# 1A18J6_1A20J11_A.net
KiCad netlist of a schematic drawn in Altium Designer
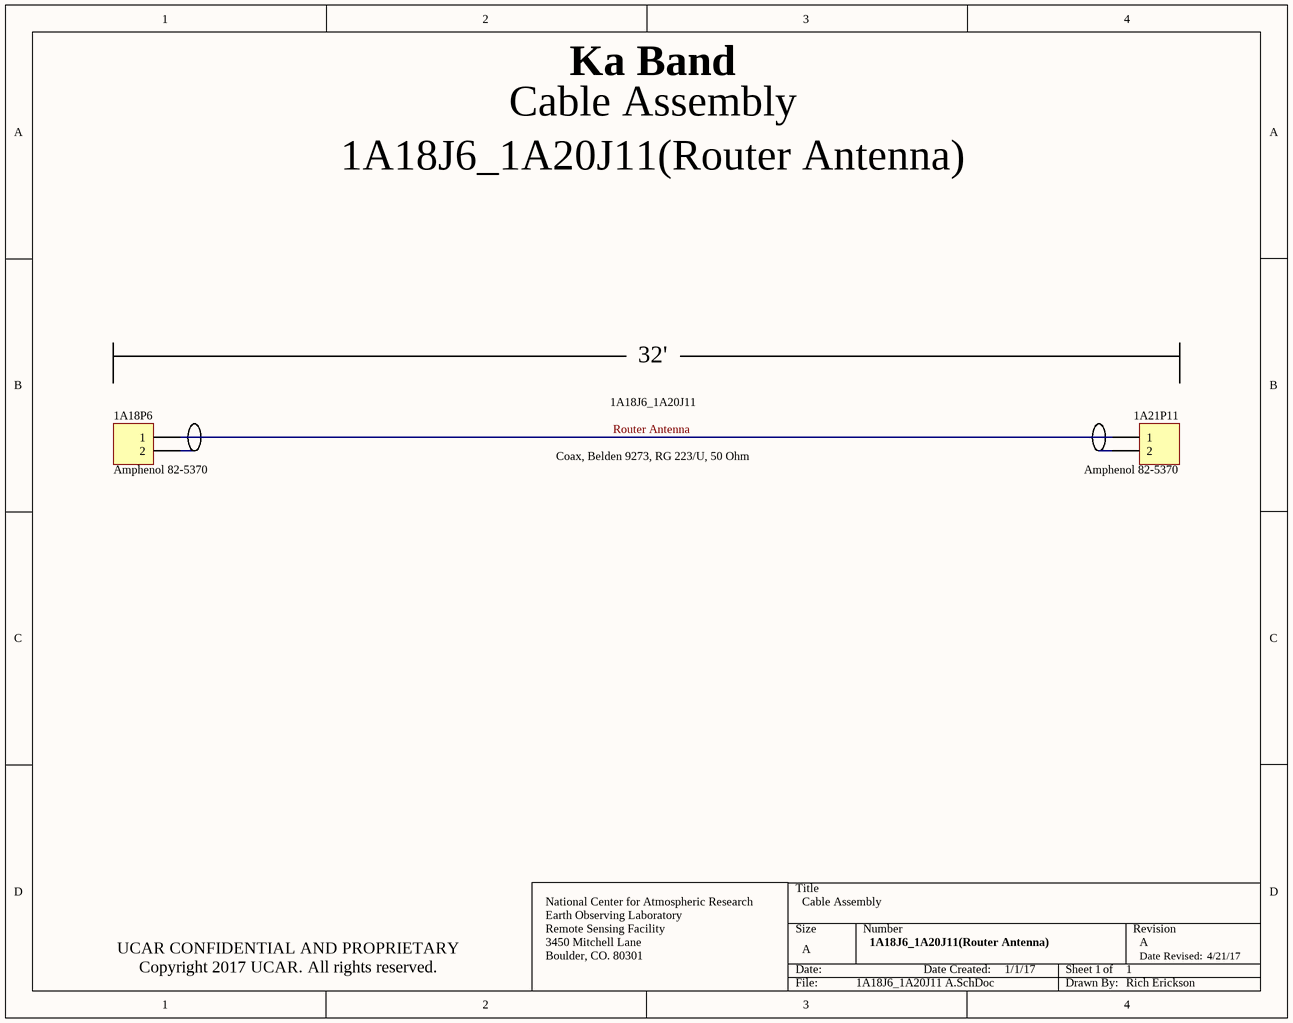
[diagram p0: 1A18J6_1A20J11 A.SchDoc]

(export (version "E")
  (design (tool "Eeschema 10.0.6"))
  (components
    (comp (ref "1A18P6")
      (value "Amphenol 82-5370")
      (footprint "HDR1X2")
      (description "Header, 2-Pin")
      (fields (field (name "PUBLISHER") "Altium Limited"))
      (libsource (lib "") (part "Header 2_1"))
    )
    (comp (ref "1A21P11")
      (value "Amphenol 82-5370")
      (footprint "HDR1X2")
      (description "Header, 2-Pin")
      (fields (field (name "PUBLISHER") "Altium Limited"))
      (libsource (lib "Miscellaneous Connectors") (part "Header 2"))
    )
  )
  (nets
    (net (code "1") (name "/Router Antenna") (class "Default")
      (node (ref "1A18P6") (pin "1") (pinfunction "1_1") (pintype "passive"))
      (node (ref "1A21P11") (pin "1") (pinfunction "1_1") (pintype "passive"))
    )
    (net (code "2") (name "unconnected-(1A18P6-Pad2)") (class "Default")
      (node (ref "1A18P6") (pin "2") (pinfunction "2_2") (pintype "passive"))
    )
    (net (code "3") (name "unconnected-(1A21P11-Pad2)") (class "Default")
      (node (ref "1A21P11") (pin "2") (pinfunction "2_2") (pintype "passive"))
    )
  )
)
